# knuckleboard.net
KiCad netlist of a schematic drawn in EAGLE
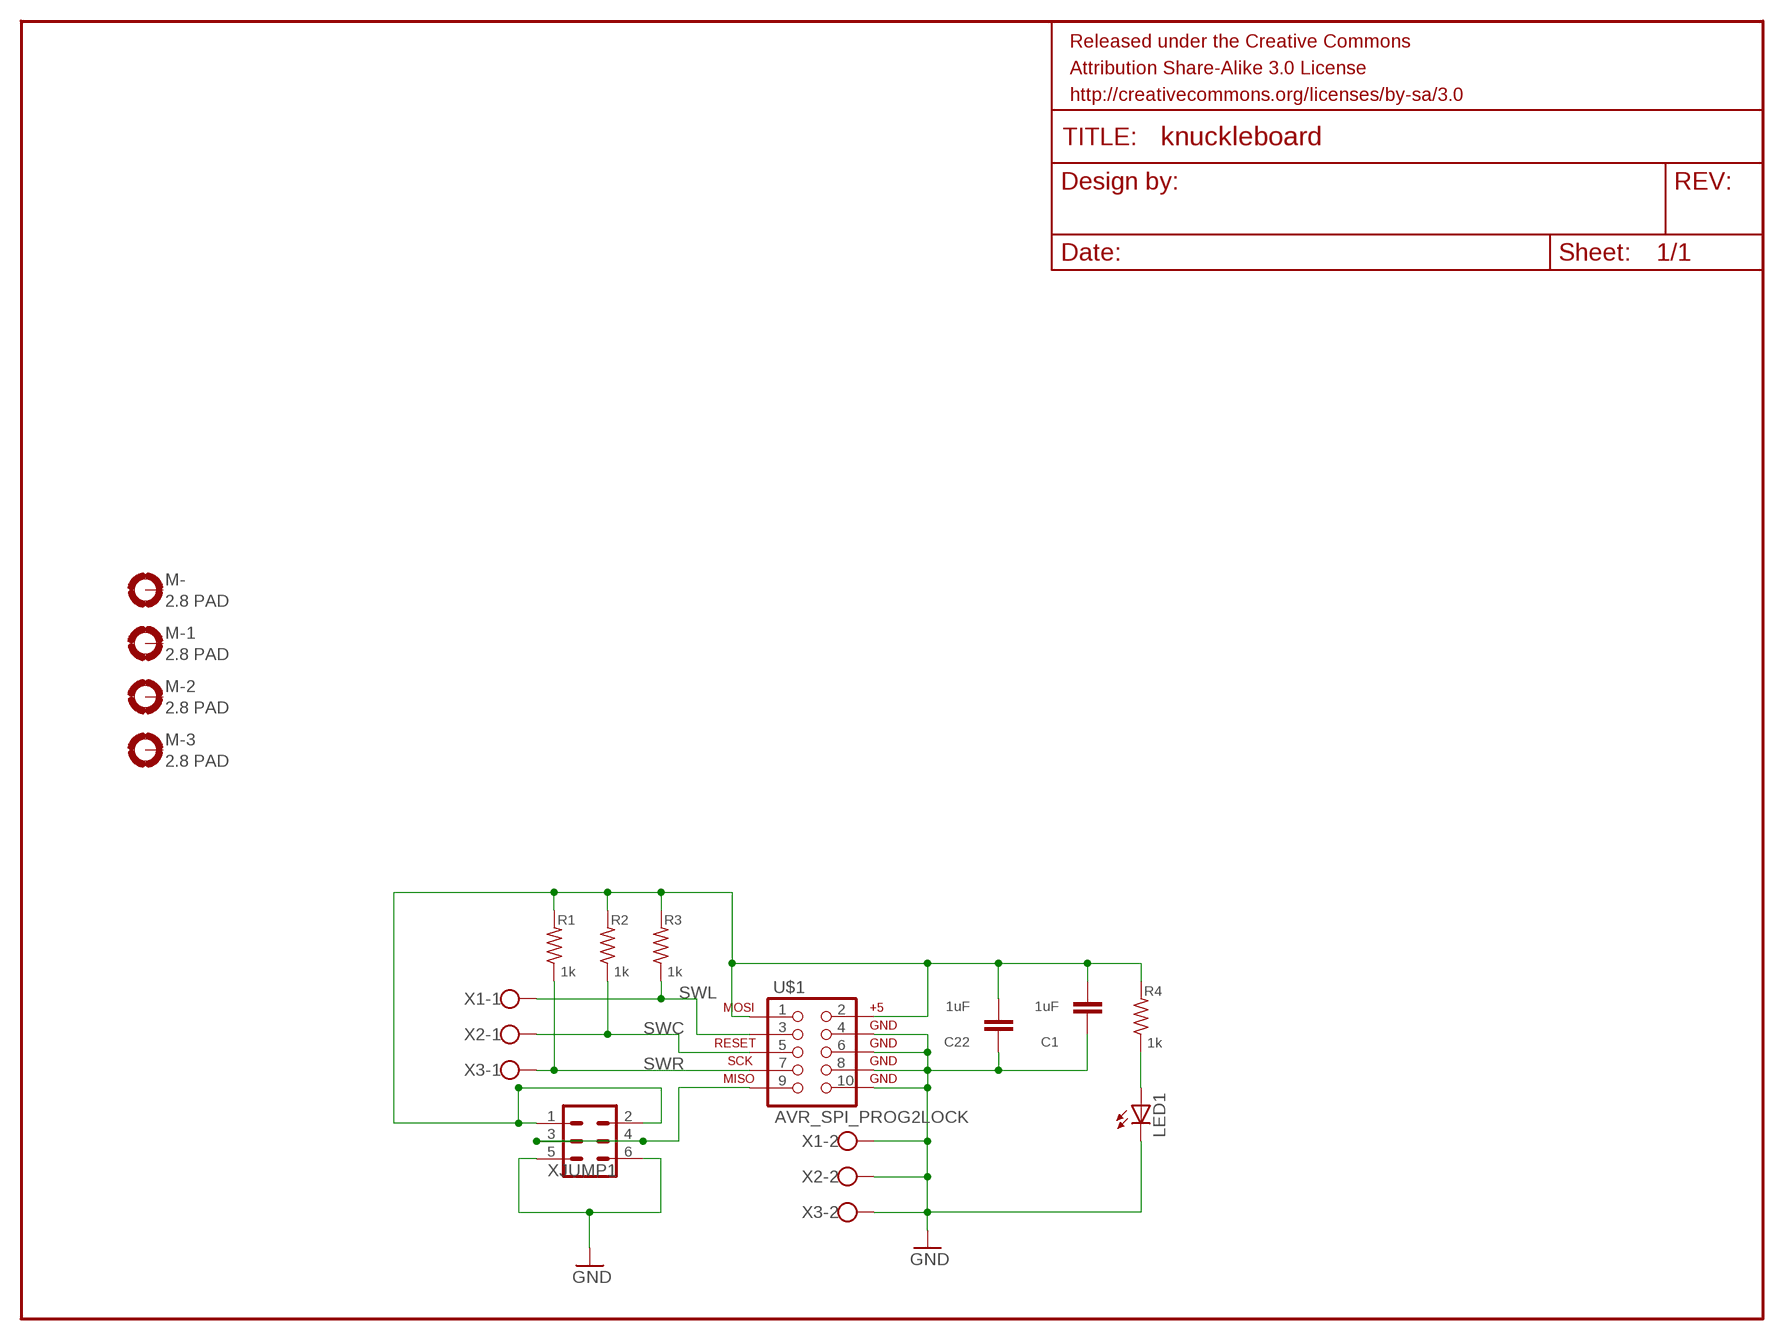
[diagram p0: schematic, sheet 1]

(export (version "E")
  (design (tool "Eeschema 10.0.6"))
  (components
    (comp (ref "C1")
      (value "1uF")
      (footprint "eagle-import:C1206")
      (libsource (lib "eagle-import") (part "C-EUC1206"))
    )
    (comp (ref "C22")
      (value "1uF")
      (footprint "eagle-import:C1206")
      (libsource (lib "eagle-import") (part "C-EUC1206"))
    )
    (comp (ref "LED1")
      (value "LEDCHIPLED_1206")
      (footprint "eagle-import:CHIPLED_1206")
      (libsource (lib "eagle-import") (part "LEDCHIPLED_1206"))
    )
    (comp (ref "M-")
      (value "2.8 PAD")
      (footprint "eagle-import:2,8-PAD")
      (libsource (lib "eagle-import") (part "MOUNT-PAD-ROUND2.8"))
    )
    (comp (ref "M-1")
      (value "2.8 PAD")
      (footprint "eagle-import:2,8-PAD")
      (libsource (lib "eagle-import") (part "MOUNT-PAD-ROUND2.8"))
    )
    (comp (ref "M-2")
      (value "2.8 PAD")
      (footprint "eagle-import:2,8-PAD")
      (libsource (lib "eagle-import") (part "MOUNT-PAD-ROUND2.8"))
    )
    (comp (ref "M-3")
      (value "2.8 PAD")
      (footprint "eagle-import:2,8-PAD")
      (libsource (lib "eagle-import") (part "MOUNT-PAD-ROUND2.8"))
    )
    (comp (ref "R1")
      (value "1k")
      (footprint "eagle-import:M1206")
      (libsource (lib "eagle-import") (part "R-US_M1206"))
    )
    (comp (ref "R2")
      (value "1k")
      (footprint "eagle-import:M1206")
      (libsource (lib "eagle-import") (part "R-US_M1206"))
    )
    (comp (ref "R3")
      (value "1k")
      (footprint "eagle-import:M1206")
      (libsource (lib "eagle-import") (part "R-US_M1206"))
    )
    (comp (ref "R4")
      (value "1k")
      (footprint "eagle-import:M1206")
      (libsource (lib "eagle-import") (part "R-US_M1206"))
    )
    (comp (ref "U$1")
      (value "AVR_SPI_PROG2LOCK")
      (footprint "eagle-import:2X5-SHROUDED_LOCK")
      (libsource (lib "eagle-import") (part "AVR_SPI_PROG2LOCK"))
    )
    (comp (ref "X1")
      (value "W237-102")
      (footprint "eagle-import:W237-102")
      (libsource (lib "eagle-import") (part "W237-102"))
    )
    (comp (ref "X2")
      (value "W237-102")
      (footprint "eagle-import:W237-102")
      (libsource (lib "eagle-import") (part "W237-102"))
    )
    (comp (ref "X3")
      (value "W237-102")
      (footprint "eagle-import:W237-102")
      (libsource (lib "eagle-import") (part "W237-102"))
    )
    (comp (ref "XJUMP1")
      (value "MA03-2")
      (footprint "eagle-import:MA03-2")
      (libsource (lib "eagle-import") (part "MA03-2"))
    )
  )
  (nets
    (net (code "1") (name "/SWC") (class "Default")
      (node (ref "R2") (pin "1") (pinfunction "1_1") (pintype "passive"))
      (node (ref "U$1") (pin "5") (pinfunction "5_5") (pintype "passive"))
      (node (ref "X2") (pin "1") (pinfunction "KL_1") (pintype "passive"))
    )
    (net (code "2") (name "/SWL") (class "Default")
      (node (ref "R3") (pin "1") (pinfunction "1_1") (pintype "passive"))
      (node (ref "U$1") (pin "3") (pinfunction "3_3") (pintype "passive"))
      (node (ref "X1") (pin "1") (pinfunction "KL_1") (pintype "passive"))
    )
    (net (code "3") (name "/SWR") (class "Default")
      (node (ref "R1") (pin "1") (pinfunction "1_1") (pintype "passive"))
      (node (ref "U$1") (pin "7") (pinfunction "7_7") (pintype "passive"))
      (node (ref "X3") (pin "1") (pinfunction "KL_1") (pintype "passive"))
    )
    (net (code "4") (name "GND") (class "Default")
      (node (ref "C1") (pin "1") (pinfunction "1_1") (pintype "passive"))
      (node (ref "C22") (pin "1") (pinfunction "1_1") (pintype "passive"))
      (node (ref "LED1") (pin "C") (pinfunction "C_C") (pintype "passive"))
      (node (ref "U$1") (pin "10") (pinfunction "10_10") (pintype "passive"))
      (node (ref "U$1") (pin "4") (pinfunction "4_4") (pintype "passive"))
      (node (ref "U$1") (pin "6") (pinfunction "6_6") (pintype "passive"))
      (node (ref "U$1") (pin "8") (pinfunction "8_8") (pintype "passive"))
      (node (ref "X1") (pin "2") (pinfunction "KL_2") (pintype "passive"))
      (node (ref "X2") (pin "2") (pinfunction "KL_2") (pintype "passive"))
      (node (ref "X3") (pin "2") (pinfunction "KL_2") (pintype "passive"))
      (node (ref "XJUMP1") (pin "5") (pinfunction "5_5") (pintype "passive"))
      (node (ref "XJUMP1") (pin "6") (pinfunction "6_6") (pintype "passive"))
    )
    (net (code "5") (name "Net-(C1-Pad2)") (class "Default")
      (node (ref "C1") (pin "2") (pinfunction "2_2") (pintype "passive"))
      (node (ref "C22") (pin "2") (pinfunction "2_2") (pintype "passive"))
      (node (ref "R1") (pin "2") (pinfunction "2_2") (pintype "passive"))
      (node (ref "R2") (pin "2") (pinfunction "2_2") (pintype "passive"))
      (node (ref "R3") (pin "2") (pinfunction "2_2") (pintype "passive"))
      (node (ref "R4") (pin "2") (pinfunction "2_2") (pintype "passive"))
      (node (ref "U$1") (pin "1") (pinfunction "1_1") (pintype "passive"))
      (node (ref "U$1") (pin "2") (pinfunction "2_2") (pintype "passive"))
      (node (ref "XJUMP1") (pin "1") (pinfunction "1_1") (pintype "passive"))
      (node (ref "XJUMP1") (pin "2") (pinfunction "2_2") (pintype "passive"))
    )
    (net (code "6") (name "Net-(LED1-PadA)") (class "Default")
      (node (ref "LED1") (pin "A") (pinfunction "A_A") (pintype "passive"))
      (node (ref "R4") (pin "1") (pinfunction "1_1") (pintype "passive"))
    )
    (net (code "7") (name "Net-(U$1-Pad9)") (class "Default")
      (node (ref "U$1") (pin "9") (pinfunction "9_9") (pintype "passive"))
      (node (ref "XJUMP1") (pin "3") (pinfunction "3_3") (pintype "passive"))
      (node (ref "XJUMP1") (pin "4") (pinfunction "4_4") (pintype "passive"))
    )
    (net (code "8") (name "unconnected-(M--MOUNT-PadB2,8)") (class "Default")
      (node (ref "M-") (pin "B2,8") (pinfunction "MOUNT_B2,8") (pintype "passive"))
    )
    (net (code "9") (name "unconnected-(M-1-MOUNT-PadB2,8)") (class "Default")
      (node (ref "M-1") (pin "B2,8") (pinfunction "MOUNT_B2,8") (pintype "passive"))
    )
    (net (code "10") (name "unconnected-(M-2-MOUNT-PadB2,8)") (class "Default")
      (node (ref "M-2") (pin "B2,8") (pinfunction "MOUNT_B2,8") (pintype "passive"))
    )
    (net (code "11") (name "unconnected-(M-3-MOUNT-PadB2,8)") (class "Default")
      (node (ref "M-3") (pin "B2,8") (pinfunction "MOUNT_B2,8") (pintype "passive"))
    )
  )
)
